# stepper_driver.net
KiCad netlist of a schematic drawn in EAGLE
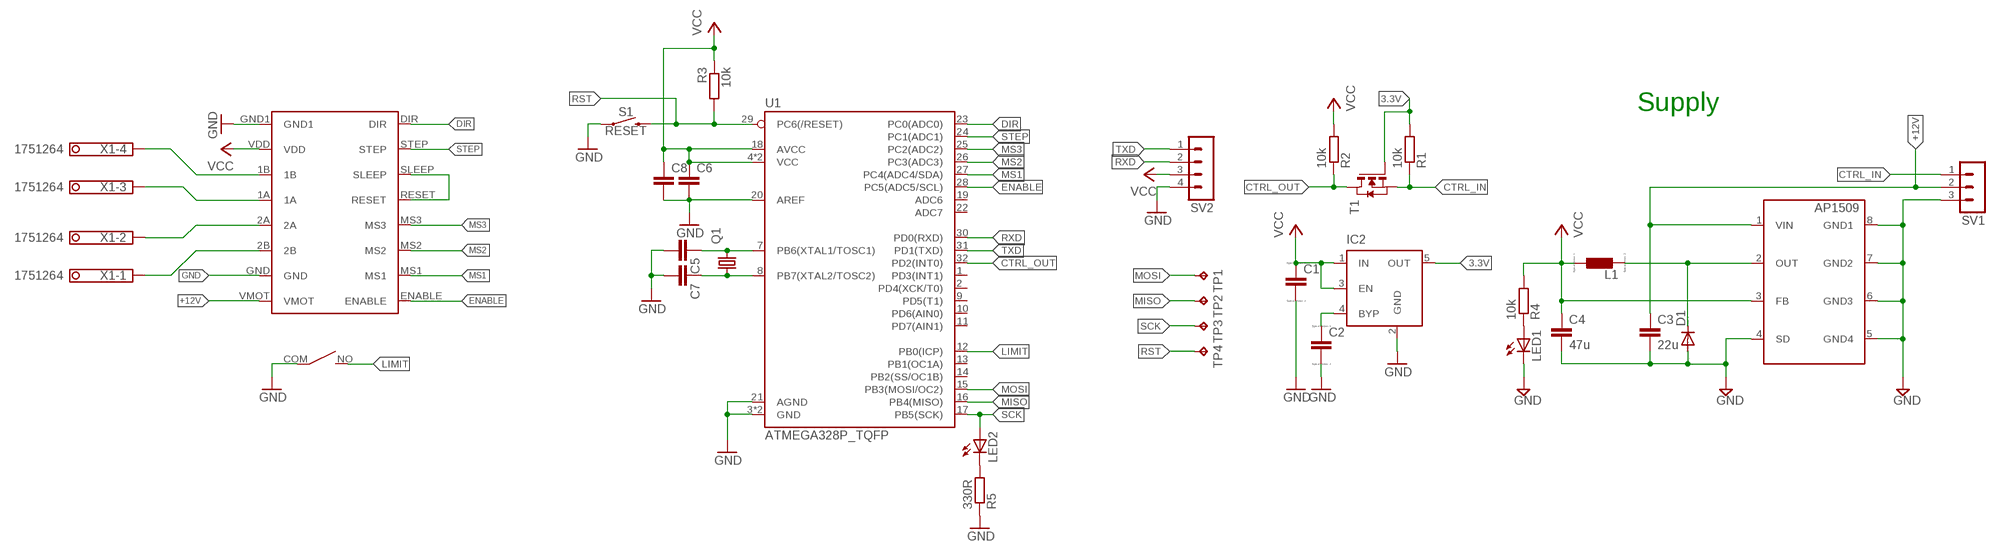
[diagram p0: schematic, sheet 1]

(export (version "E")
  (design (tool "Eeschema 10.0.6"))
  (components
    (comp (ref "C1") (value "C") (footprint "eagle-import:C0805") (libsource (lib "eagle-import") (part "C")))
    (comp (ref "C2") (value "C") (footprint "eagle-import:C0805") (libsource (lib "eagle-import") (part "C")))
    (comp (ref "C3")
      (value "22u")
      (footprint "eagle-import:C1210")
      (libsource (lib "eagle-import") (part "C-EUC1210"))
    )
    (comp (ref "C4")
      (value "47u")
      (footprint "eagle-import:C1210")
      (libsource (lib "eagle-import") (part "C-EUC1210"))
    )
    (comp (ref "C5")
      (value "C-EUC0603K")
      (footprint "eagle-import:C0603K")
      (libsource (lib "eagle-import") (part "C-EUC0603K"))
    )
    (comp (ref "C6")
      (value "C-EUC0805")
      (footprint "eagle-import:C0805")
      (libsource (lib "eagle-import") (part "C-EUC0805"))
    )
    (comp (ref "C7")
      (value "C-EUC0603K")
      (footprint "eagle-import:C0603K")
      (libsource (lib "eagle-import") (part "C-EUC0603K"))
    )
    (comp (ref "C8")
      (value "C-EUC0805")
      (footprint "eagle-import:C0805")
      (libsource (lib "eagle-import") (part "C-EUC0805"))
    )
    (comp (ref "D1")
      (value "DIODE-SOD323-W")
      (footprint "eagle-import:SOD323-W")
      (libsource (lib "eagle-import") (part "DIODE-SOD323-W"))
    )
    (comp (ref "IC2")
      (value "MIC5219XX")
      (footprint "eagle-import:SOT23-5")
      (libsource (lib "eagle-import") (part "MIC5219XX"))
    )
    (comp (ref "L1")
      (value "LL5650M")
      (footprint "eagle-import:L5650M")
      (libsource (lib "eagle-import") (part "LL5650M"))
    )
    (comp (ref "LED1")
      (value "LEDSML0805")
      (footprint "eagle-import:SML0805")
      (libsource (lib "eagle-import") (part "LEDSML0805"))
    )
    (comp (ref "LED2")
      (value "LEDSML0805")
      (footprint "eagle-import:SML0805")
      (libsource (lib "eagle-import") (part "LEDSML0805"))
    )
    (comp (ref "Q1")
      (value "KX-7")
      (footprint "eagle-import:3.2X2.5_KX-7")
      (libsource (lib "eagle-import") (part "KX-7"))
    )
    (comp (ref "R1")
      (value "10k")
      (footprint "eagle-import:R0805")
      (libsource (lib "eagle-import") (part "R-EU_R0805"))
    )
    (comp (ref "R2")
      (value "10k")
      (footprint "eagle-import:R0805")
      (libsource (lib "eagle-import") (part "R-EU_R0805"))
    )
    (comp (ref "R3")
      (value "10k")
      (footprint "eagle-import:R0805")
      (libsource (lib "eagle-import") (part "R-EU_R0805"))
    )
    (comp (ref "R4")
      (value "10k")
      (footprint "eagle-import:R0805")
      (libsource (lib "eagle-import") (part "R-EU_R0805"))
    )
    (comp (ref "R5")
      (value "330R")
      (footprint "eagle-import:R0805")
      (libsource (lib "eagle-import") (part "R-EU_R0805"))
    )
    (comp (ref "S1")
      (value "RESET")
      (footprint "eagle-import:TACTILE_SWITCH_SMD_6.0X3.5MM")
      (libsource (lib "eagle-import") (part "MOMENTARY-SWITCH-SPST-SMD-6.0X3.5MM"))
    )
    (comp (ref "SV1")
      (value "MA03-1")
      (footprint "eagle-import:MA03-1")
      (libsource (lib "eagle-import") (part "MA03-1"))
    )
    (comp (ref "SV2")
      (value "MA04-1")
      (footprint "eagle-import:MA04-1")
      (libsource (lib "eagle-import") (part "MA04-1"))
    )
    (comp (ref "T1")
      (value "NMOSSOT23")
      (footprint "eagle-import:SOT-23")
      (libsource (lib "eagle-import") (part "NMOSSOT23"))
    )
    (comp (ref "TP1")
      (value "TPTP20SQ")
      (footprint "eagle-import:TP20SQ")
      (libsource (lib "eagle-import") (part "TPTP20SQ"))
    )
    (comp (ref "TP2")
      (value "TPTP20SQ")
      (footprint "eagle-import:TP20SQ")
      (libsource (lib "eagle-import") (part "TPTP20SQ"))
    )
    (comp (ref "TP3")
      (value "TPTP20SQ")
      (footprint "eagle-import:TP20SQ")
      (libsource (lib "eagle-import") (part "TPTP20SQ"))
    )
    (comp (ref "TP4")
      (value "TPTP20SQ")
      (footprint "eagle-import:TP20SQ")
      (libsource (lib "eagle-import") (part "TPTP20SQ"))
    )
    (comp (ref "U$1")
      (value "AP1509")
      (footprint "eagle-import:SOP08")
      (libsource (lib "eagle-import") (part "AP1509"))
    )
    (comp (ref "U$2")
      (value "A4988MODULE")
      (footprint "eagle-import:A4988")
      (libsource (lib "eagle-import") (part "A4988MODULE"))
    )
    (comp (ref "U$3")
      (value "D2S")
      (footprint "eagle-import:D2S")
      (libsource (lib "eagle-import") (part "D2S"))
    )
    (comp (ref "U1")
      (value "ATMEGA328P_TQFP")
      (footprint "eagle-import:TQFP32-08")
      (libsource (lib "eagle-import") (part "ATMEGA328P_TQFP"))
    )
    (comp (ref "X1")
      (value "1751264")
      (footprint "eagle-import:1751264")
      (libsource (lib "eagle-import") (part "1751264"))
    )
  )
  (nets
    (net (code "1") (name "+12V") (class "Default")
      (node (ref "C3") (pin "1") (pinfunction "1_1") (pintype "passive"))
      (node (ref "SV1") (pin "2") (pinfunction "2_2") (pintype "passive"))
      (node (ref "U$1") (pin "1") (pinfunction "VIN_1") (pintype "bidirectional"))
      (node (ref "U$2") (pin "VMOT") (pinfunction "VMOT_VMOT") (pintype "bidirectional"))
    )
    (net (code "2") (name "3.3V") (class "Default")
      (node (ref "IC2") (pin "5") (pinfunction "OUT_5") (pintype "output"))
      (node (ref "R1") (pin "2") (pinfunction "2_2") (pintype "passive"))
      (node (ref "T1") (pin "3") (pinfunction "G_3") (pintype "passive"))
    )
    (net (code "3") (name "CTRL_IN") (class "Default")
      (node (ref "R1") (pin "1") (pinfunction "1_1") (pintype "passive"))
      (node (ref "SV1") (pin "1") (pinfunction "1_1") (pintype "passive"))
      (node (ref "T1") (pin "2") (pinfunction "S_2") (pintype "passive"))
    )
    (net (code "4") (name "CTRL_OUT") (class "Default")
      (node (ref "R2") (pin "1") (pinfunction "1_1") (pintype "passive"))
      (node (ref "T1") (pin "1") (pinfunction "D_1") (pintype "passive"))
      (node (ref "U1") (pin "32") (pinfunction "PD2(INT0)_32") (pintype "bidirectional"))
    )
    (net (code "5") (name "DIR") (class "Default")
      (node (ref "U$2") (pin "DIR") (pinfunction "DIR_DIR") (pintype "bidirectional"))
      (node (ref "U1") (pin "23") (pinfunction "PC0(ADC0)_23") (pintype "bidirectional"))
    )
    (net (code "6") (name "ENABLE") (class "Default")
      (node (ref "U$2") (pin "ENABLE") (pinfunction "ENABLE_ENABLE") (pintype "bidirectional"))
      (node (ref "U1") (pin "28") (pinfunction "PC5(ADC5/SCL)_28") (pintype "bidirectional"))
    )
    (net (code "7") (name "GND") (class "Default")
      (node (ref "C1") (pin "2") (pinfunction "2_2") (pintype "passive"))
      (node (ref "C2") (pin "2") (pinfunction "2_2") (pintype "passive"))
      (node (ref "C3") (pin "2") (pinfunction "2_2") (pintype "passive"))
      (node (ref "C4") (pin "2") (pinfunction "2_2") (pintype "passive"))
      (node (ref "C5") (pin "2") (pinfunction "2_2") (pintype "passive"))
      (node (ref "C6") (pin "2") (pinfunction "2_2") (pintype "passive"))
      (node (ref "C7") (pin "2") (pinfunction "2_2") (pintype "passive"))
      (node (ref "C8") (pin "2") (pinfunction "2_2") (pintype "passive"))
      (node (ref "D1") (pin "A") (pinfunction "A_A") (pintype "passive"))
      (node (ref "IC2") (pin "2") (pinfunction "GND_2") (pintype "power_in"))
      (node (ref "LED1") (pin "C") (pinfunction "C_C") (pintype "passive"))
      (node (ref "R5") (pin "1") (pinfunction "1_1") (pintype "passive"))
      (node (ref "S1") (pin "1") (pinfunction "1_1") (pintype "passive"))
      (node (ref "SV1") (pin "3") (pinfunction "3_3") (pintype "passive"))
      (node (ref "SV2") (pin "4") (pinfunction "4_4") (pintype "passive"))
      (node (ref "U$1") (pin "4") (pinfunction "SD_4") (pintype "bidirectional"))
      (node (ref "U$1") (pin "5") (pinfunction "GND4_5") (pintype "bidirectional"))
      (node (ref "U$1") (pin "6") (pinfunction "GND3_6") (pintype "bidirectional"))
      (node (ref "U$1") (pin "7") (pinfunction "GND2_7") (pintype "bidirectional"))
      (node (ref "U$1") (pin "8") (pinfunction "GND1_8") (pintype "bidirectional"))
      (node (ref "U$2") (pin "GND") (pinfunction "GND_GND") (pintype "bidirectional"))
      (node (ref "U$2") (pin "GND1") (pinfunction "GND1_GND1") (pintype "bidirectional"))
      (node (ref "U$3") (pin "COM") (pinfunction "COM_COM") (pintype "bidirectional"))
      (node (ref "U1") (pin "20") (pinfunction "AREF_20") (pintype "bidirectional"))
      (node (ref "U1") (pin "21") (pinfunction "AGND_21") (pintype "bidirectional"))
      (node (ref "U1") (pin "3") (pinfunction "GND_3") (pintype "bidirectional"))
      (node (ref "U1") (pin "5") (pinfunction "GND_5") (pintype "bidirectional"))
    )
    (net (code "8") (name "LIMIT") (class "Default")
      (node (ref "U$3") (pin "NO") (pinfunction "NO_NO") (pintype "bidirectional"))
      (node (ref "U1") (pin "12") (pinfunction "PB0(ICP)_12") (pintype "bidirectional"))
    )
    (net (code "9") (name "MISO") (class "Default")
      (node (ref "TP2") (pin "TP") (pinfunction "TP_TP") (pintype "input"))
      (node (ref "U1") (pin "16") (pinfunction "PB4(MISO)_16") (pintype "bidirectional"))
    )
    (net (code "10") (name "MOSI") (class "Default")
      (node (ref "TP1") (pin "TP") (pinfunction "TP_TP") (pintype "input"))
      (node (ref "U1") (pin "15") (pinfunction "PB3(MOSI/OC2)_15") (pintype "bidirectional"))
    )
    (net (code "11") (name "MS1") (class "Default")
      (node (ref "U$2") (pin "MS1") (pinfunction "MS1_MS1") (pintype "bidirectional"))
      (node (ref "U1") (pin "27") (pinfunction "PC4(ADC4/SDA)_27") (pintype "bidirectional"))
    )
    (net (code "12") (name "MS2") (class "Default")
      (node (ref "U$2") (pin "MS2") (pinfunction "MS2_MS2") (pintype "bidirectional"))
      (node (ref "U1") (pin "26") (pinfunction "PC3(ADC3)_26") (pintype "bidirectional"))
    )
    (net (code "13") (name "MS3") (class "Default")
      (node (ref "U$2") (pin "MS3") (pinfunction "MS3_MS3") (pintype "bidirectional"))
      (node (ref "U1") (pin "25") (pinfunction "PC2(ADC2)_25") (pintype "bidirectional"))
    )
    (net (code "14") (name "Net-(IC2-BYP)") (class "Default")
      (node (ref "C2") (pin "1") (pinfunction "1_1") (pintype "passive"))
      (node (ref "IC2") (pin "4") (pinfunction "BYP_4") (pintype "passive"))
    )
    (net (code "15") (name "Net-(LED1-PadA)") (class "Default")
      (node (ref "LED1") (pin "A") (pinfunction "A_A") (pintype "passive"))
      (node (ref "R4") (pin "1") (pinfunction "1_1") (pintype "passive"))
    )
    (net (code "16") (name "Net-(LED2-PadC)") (class "Default")
      (node (ref "LED2") (pin "C") (pinfunction "C_C") (pintype "passive"))
      (node (ref "R5") (pin "2") (pinfunction "2_2") (pintype "passive"))
    )
    (net (code "17") (name "Net-(Q1-2)") (class "Default")
      (node (ref "C5") (pin "1") (pinfunction "1_1") (pintype "passive"))
      (node (ref "Q1") (pin "3") (pinfunction "2_3") (pintype "passive"))
      (node (ref "U1") (pin "7") (pinfunction "PB6(XTAL1/TOSC1)_7") (pintype "bidirectional"))
    )
    (net (code "18") (name "Net-(U$1-OUT)") (class "Default")
      (node (ref "D1") (pin "C") (pinfunction "C_C") (pintype "passive"))
      (node (ref "L1") (pin "2") (pinfunction "2_2") (pintype "passive"))
      (node (ref "U$1") (pin "2") (pinfunction "OUT_2") (pintype "bidirectional"))
    )
    (net (code "19") (name "Net-(U$2-PadRESET)") (class "Default")
      (node (ref "U$2") (pin "RESET") (pinfunction "RESET_RESET") (pintype "bidirectional"))
      (node (ref "U$2") (pin "SLEEP") (pinfunction "SLEEP_SLEEP") (pintype "bidirectional"))
    )
    (net (code "20") (name "Net-(U1-PB7(XTAL2{slash}TOSC2))") (class "Default")
      (node (ref "C7") (pin "1") (pinfunction "1_1") (pintype "passive"))
      (node (ref "Q1") (pin "1") (pinfunction "1_1") (pintype "passive"))
      (node (ref "U1") (pin "8") (pinfunction "PB7(XTAL2/TOSC2)_8") (pintype "bidirectional"))
    )
    (net (code "21") (name "Net-(X1A-K)") (class "Default")
      (node (ref "U$2") (pin "2B") (pinfunction "2B_2B") (pintype "bidirectional"))
      (node (ref "X1") (pin "1") (pinfunction "K_1") (pintype "passive"))
    )
    (net (code "22") (name "Net-(X1B-K)") (class "Default")
      (node (ref "U$2") (pin "2A") (pinfunction "2A_2A") (pintype "bidirectional"))
      (node (ref "X1") (pin "2") (pinfunction "K_2") (pintype "passive"))
    )
    (net (code "23") (name "Net-(X1C-K)") (class "Default")
      (node (ref "U$2") (pin "1A") (pinfunction "1A_1A") (pintype "bidirectional"))
      (node (ref "X1") (pin "3") (pinfunction "K_3") (pintype "passive"))
    )
    (net (code "24") (name "Net-(X1D-K)") (class "Default")
      (node (ref "U$2") (pin "1B") (pinfunction "1B_1B") (pintype "bidirectional"))
      (node (ref "X1") (pin "4") (pinfunction "K_4") (pintype "passive"))
    )
    (net (code "25") (name "RST") (class "Default")
      (node (ref "R3") (pin "2") (pinfunction "2_2") (pintype "passive"))
      (node (ref "S1") (pin "2") (pinfunction "2_2") (pintype "passive"))
      (node (ref "TP4") (pin "TP") (pinfunction "TP_TP") (pintype "input"))
      (node (ref "U1") (pin "29") (pinfunction "PC6(/RESET)_29") (pintype "bidirectional"))
    )
    (net (code "26") (name "RXD") (class "Default")
      (node (ref "SV2") (pin "2") (pinfunction "2_2") (pintype "passive"))
      (node (ref "U1") (pin "30") (pinfunction "PD0(RXD)_30") (pintype "bidirectional"))
    )
    (net (code "27") (name "SCK") (class "Default")
      (node (ref "LED2") (pin "A") (pinfunction "A_A") (pintype "passive"))
      (node (ref "TP3") (pin "TP") (pinfunction "TP_TP") (pintype "input"))
      (node (ref "U1") (pin "17") (pinfunction "PB5(SCK)_17") (pintype "bidirectional"))
    )
    (net (code "28") (name "STEP") (class "Default")
      (node (ref "U$2") (pin "STEP") (pinfunction "STEP_STEP") (pintype "bidirectional"))
      (node (ref "U1") (pin "24") (pinfunction "PC1(ADC1)_24") (pintype "bidirectional"))
    )
    (net (code "29") (name "TXD") (class "Default")
      (node (ref "SV2") (pin "1") (pinfunction "1_1") (pintype "passive"))
      (node (ref "U1") (pin "31") (pinfunction "PD1(TXD)_31") (pintype "bidirectional"))
    )
    (net (code "30") (name "VCC") (class "Default")
      (node (ref "C1") (pin "1") (pinfunction "1_1") (pintype "passive"))
      (node (ref "C4") (pin "1") (pinfunction "1_1") (pintype "passive"))
      (node (ref "C6") (pin "1") (pinfunction "1_1") (pintype "passive"))
      (node (ref "C8") (pin "1") (pinfunction "1_1") (pintype "passive"))
      (node (ref "IC2") (pin "1") (pinfunction "IN_1") (pintype "input"))
      (node (ref "IC2") (pin "3") (pinfunction "EN_3") (pintype "input"))
      (node (ref "L1") (pin "1") (pinfunction "1_1") (pintype "passive"))
      (node (ref "R2") (pin "2") (pinfunction "2_2") (pintype "passive"))
      (node (ref "R3") (pin "1") (pinfunction "1_1") (pintype "passive"))
      (node (ref "R4") (pin "2") (pinfunction "2_2") (pintype "passive"))
      (node (ref "SV2") (pin "3") (pinfunction "3_3") (pintype "passive"))
      (node (ref "U$1") (pin "3") (pinfunction "FB_3") (pintype "bidirectional"))
      (node (ref "U$2") (pin "VDD") (pinfunction "VDD_VDD") (pintype "bidirectional"))
      (node (ref "U1") (pin "18") (pinfunction "AVCC_18") (pintype "bidirectional"))
      (node (ref "U1") (pin "4") (pinfunction "VCC_4") (pintype "bidirectional"))
      (node (ref "U1") (pin "6") (pinfunction "VCC_6") (pintype "bidirectional"))
    )
    (net (code "31") (name "unconnected-(U1-ADC6-Pad19)") (class "Default")
      (node (ref "U1") (pin "19") (pinfunction "ADC6_19") (pintype "bidirectional"))
    )
    (net (code "32") (name "unconnected-(U1-ADC7-Pad22)") (class "Default")
      (node (ref "U1") (pin "22") (pinfunction "ADC7_22") (pintype "bidirectional"))
    )
    (net (code "33") (name "unconnected-(U1-PB1(OC1A)-Pad13)") (class "Default")
      (node (ref "U1") (pin "13") (pinfunction "PB1(OC1A)_13") (pintype "bidirectional"))
    )
    (net (code "34") (name "unconnected-(U1-PB2(SS{slash}OC1B)-Pad14)") (class "Default")
      (node (ref "U1") (pin "14") (pinfunction "PB2(SS/OC1B)_14") (pintype "bidirectional"))
    )
    (net (code "35") (name "unconnected-(U1-PD3(INT1)-Pad1)") (class "Default")
      (node (ref "U1") (pin "1") (pinfunction "PD3(INT1)_1") (pintype "bidirectional"))
    )
    (net (code "36") (name "unconnected-(U1-PD4(XCK{slash}T0)-Pad2)") (class "Default")
      (node (ref "U1") (pin "2") (pinfunction "PD4(XCK/T0)_2") (pintype "bidirectional"))
    )
    (net (code "37") (name "unconnected-(U1-PD5(T1)-Pad9)") (class "Default")
      (node (ref "U1") (pin "9") (pinfunction "PD5(T1)_9") (pintype "bidirectional"))
    )
    (net (code "38") (name "unconnected-(U1-PD6(AIN0)-Pad10)") (class "Default")
      (node (ref "U1") (pin "10") (pinfunction "PD6(AIN0)_10") (pintype "bidirectional"))
    )
    (net (code "39") (name "unconnected-(U1-PD7(AIN1)-Pad11)") (class "Default")
      (node (ref "U1") (pin "11") (pinfunction "PD7(AIN1)_11") (pintype "bidirectional"))
    )
  )
)
